# zik-pcb-power.net
KiCad netlist of a schematic drawn in EAGLE
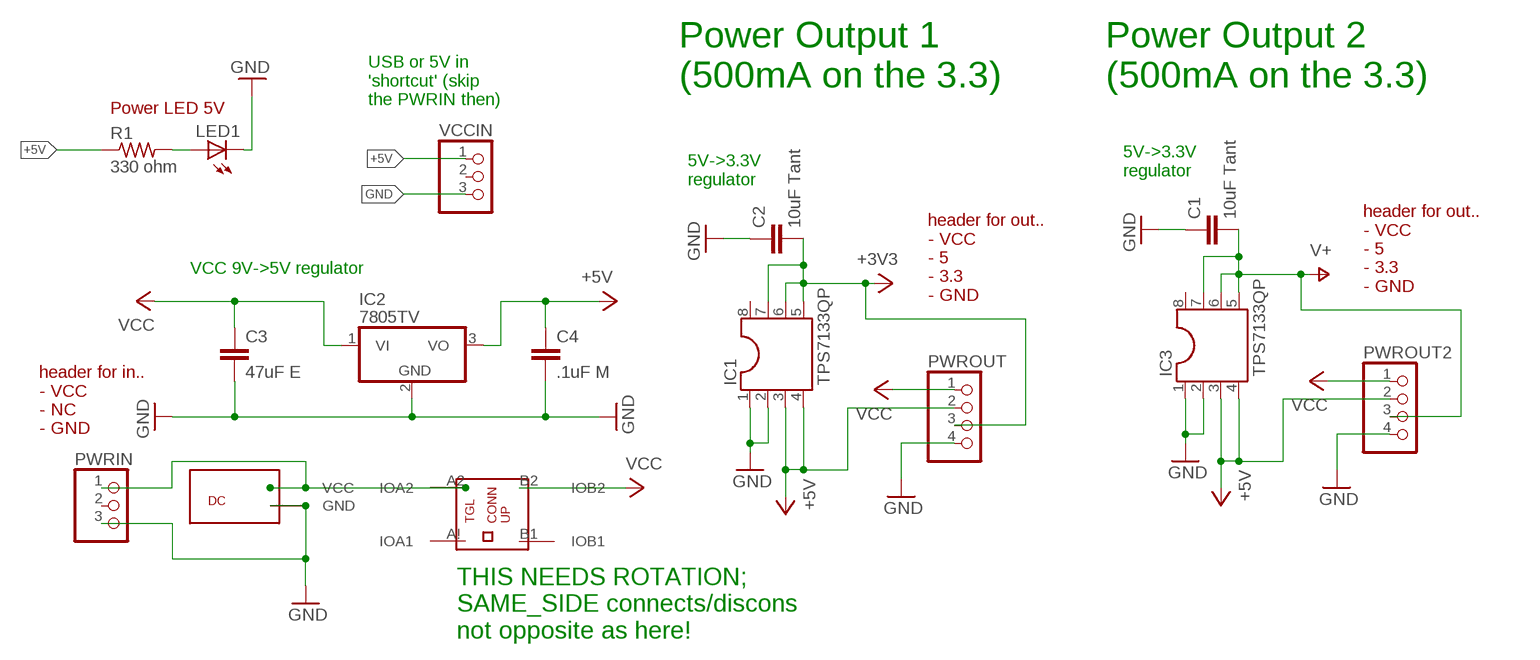
[diagram p0: schematic, sheet 1]

(export (version "E")
  (design (tool "Eeschema 10.0.6"))
  (components
    (comp (ref "C1")
      (value "10uF Tant")
      (footprint "eagle-import:C025-025X050")
      (libsource (lib "eagle-import") (part "C-EU025-025X050"))
    )
    (comp (ref "C2")
      (value "10uF Tant")
      (footprint "eagle-import:C025-025X050")
      (libsource (lib "eagle-import") (part "C-EU025-025X050"))
    )
    (comp (ref "C3")
      (value "47uF E")
      (footprint "eagle-import:C025-025X050")
      (libsource (lib "eagle-import") (part "C-EU025-025X050"))
    )
    (comp (ref "C4")
      (value ".1uF M")
      (footprint "eagle-import:C025-025X050")
      (libsource (lib "eagle-import") (part "C-EU025-025X050"))
    )
    (comp (ref "IC1")
      (value "TPS7133QP")
      (footprint "eagle-import:DIL08")
      (libsource (lib "eagle-import") (part "DIL8"))
    )
    (comp (ref "IC2")
      (value "7805TV")
      (footprint "eagle-import:TO220V")
      (libsource (lib "eagle-import") (part "78TV05"))
    )
    (comp (ref "IC3")
      (value "TPS7133QP")
      (footprint "eagle-import:DIL08")
      (libsource (lib "eagle-import") (part "DIL8"))
    )
    (comp (ref "LED1")
      (value "LED5MM")
      (footprint "eagle-import:LED5MM")
      (libsource (lib "eagle-import") (part "LED5MM"))
    )
    (comp (ref "PWRIN")
      (value "PINHD-1X3")
      (footprint "eagle-import:1X03")
      (libsource (lib "eagle-import") (part "PINHD-1X3"))
    )
    (comp (ref "PWROUT")
      (value "PINHD-1X4")
      (footprint "eagle-import:1X04")
      (libsource (lib "eagle-import") (part "PINHD-1X4"))
    )
    (comp (ref "PWROUT2")
      (value "PINHD-1X4")
      (footprint "eagle-import:1X04")
      (libsource (lib "eagle-import") (part "PINHD-1X4"))
    )
    (comp (ref "R1")
      (value "330 ohm")
      (footprint "eagle-import:0207_10")
      (libsource (lib "eagle-import") (part "R-US_0207/10"))
    )
    (comp (ref "U$1")
      (value "DCJACKZIK")
      (footprint "eagle-import:DCJACKZIK")
      (libsource (lib "eagle-import") (part "DCJACKZIK"))
    )
    (comp (ref "U$2")
      (value "TOGGLE-CYAN-L-ZIK")
      (footprint "eagle-import:TOGGLE-CYAN-LG-ZIK")
      (libsource (lib "eagle-import") (part "TOGGLE-CYAN-L-ZIK"))
    )
    (comp (ref "VCCIN")
      (value "PINHD-1X3")
      (footprint "eagle-import:1X03")
      (libsource (lib "eagle-import") (part "PINHD-1X3"))
    )
  )
  (nets
    (net (code "1") (name "+3V3") (class "Default")
      (node (ref "C2") (pin "2") (pinfunction "2_2") (pintype "passive"))
      (node (ref "IC1") (pin "5") (pinfunction "5_5") (pintype "passive"))
      (node (ref "IC1") (pin "6") (pinfunction "6_6") (pintype "passive"))
      (node (ref "IC1") (pin "7") (pinfunction "7_7") (pintype "passive"))
      (node (ref "PWROUT") (pin "3") (pinfunction "3_3") (pintype "passive"))
    )
    (net (code "2") (name "+5V") (class "Default")
      (node (ref "C4") (pin "1") (pinfunction "1_1") (pintype "passive"))
      (node (ref "IC1") (pin "3") (pinfunction "3_3") (pintype "passive"))
      (node (ref "IC1") (pin "4") (pinfunction "4_4") (pintype "passive"))
      (node (ref "IC2") (pin "3") (pinfunction "VO_3") (pintype "passive"))
      (node (ref "IC3") (pin "3") (pinfunction "3_3") (pintype "passive"))
      (node (ref "IC3") (pin "4") (pinfunction "4_4") (pintype "passive"))
      (node (ref "PWROUT") (pin "2") (pinfunction "2_2") (pintype "passive"))
      (node (ref "PWROUT2") (pin "2") (pinfunction "2_2") (pintype "passive"))
      (node (ref "R1") (pin "1") (pinfunction "1_1") (pintype "passive"))
      (node (ref "VCCIN") (pin "1") (pinfunction "1_1") (pintype "passive"))
    )
    (net (code "3") (name "GND") (class "Default")
      (node (ref "C1") (pin "1") (pinfunction "1_1") (pintype "passive"))
      (node (ref "C2") (pin "1") (pinfunction "1_1") (pintype "passive"))
      (node (ref "C3") (pin "2") (pinfunction "2_2") (pintype "passive"))
      (node (ref "C4") (pin "2") (pinfunction "2_2") (pintype "passive"))
      (node (ref "IC1") (pin "1") (pinfunction "1_1") (pintype "passive"))
      (node (ref "IC1") (pin "2") (pinfunction "2_2") (pintype "passive"))
      (node (ref "IC2") (pin "2") (pinfunction "GND_2") (pintype "passive"))
      (node (ref "IC3") (pin "1") (pinfunction "1_1") (pintype "passive"))
      (node (ref "IC3") (pin "2") (pinfunction "2_2") (pintype "passive"))
      (node (ref "LED1") (pin "K") (pinfunction "C_K") (pintype "passive"))
      (node (ref "PWRIN") (pin "3") (pinfunction "3_3") (pintype "passive"))
      (node (ref "PWROUT") (pin "4") (pinfunction "4_4") (pintype "passive"))
      (node (ref "PWROUT2") (pin "4") (pinfunction "4_4") (pintype "passive"))
      (node (ref "U$1") (pin "JACKET") (pinfunction "GND_JACKET") (pintype "power_in"))
      (node (ref "VCCIN") (pin "3") (pinfunction "3_3") (pintype "passive"))
    )
    (net (code "4") (name "Net-(LED1-PadA)") (class "Default")
      (node (ref "LED1") (pin "A") (pinfunction "A_A") (pintype "passive"))
      (node (ref "R1") (pin "2") (pinfunction "2_2") (pintype "passive"))
    )
    (net (code "5") (name "Net-(U$1-VCC)") (class "Default")
      (node (ref "PWRIN") (pin "1") (pinfunction "1_1") (pintype "passive"))
      (node (ref "U$1") (pin "CPIN") (pinfunction "VCC_CPIN") (pintype "power_in"))
      (node (ref "U$2") (pin "A2") (pinfunction "IOA2_A2") (pintype "bidirectional"))
    )
    (net (code "6") (name "V+") (class "Default")
      (node (ref "C1") (pin "2") (pinfunction "2_2") (pintype "passive"))
      (node (ref "IC3") (pin "5") (pinfunction "5_5") (pintype "passive"))
      (node (ref "IC3") (pin "6") (pinfunction "6_6") (pintype "passive"))
      (node (ref "IC3") (pin "7") (pinfunction "7_7") (pintype "passive"))
      (node (ref "PWROUT2") (pin "3") (pinfunction "3_3") (pintype "passive"))
    )
    (net (code "7") (name "VCC") (class "Default")
      (node (ref "C3") (pin "1") (pinfunction "1_1") (pintype "passive"))
      (node (ref "IC2") (pin "1") (pinfunction "VI_1") (pintype "input"))
      (node (ref "PWROUT") (pin "1") (pinfunction "1_1") (pintype "passive"))
      (node (ref "PWROUT2") (pin "1") (pinfunction "1_1") (pintype "passive"))
      (node (ref "U$2") (pin "B2") (pinfunction "IOB2_B2") (pintype "bidirectional"))
    )
    (net (code "8") (name "unconnected-(IC1-Pad8)") (class "Default")
      (node (ref "IC1") (pin "8") (pinfunction "8_8") (pintype "passive"))
    )
    (net (code "9") (name "unconnected-(IC3-Pad8)") (class "Default")
      (node (ref "IC3") (pin "8") (pinfunction "8_8") (pintype "passive"))
    )
    (net (code "10") (name "unconnected-(PWRIN-Pad2)") (class "Default")
      (node (ref "PWRIN") (pin "2") (pinfunction "2_2") (pintype "passive"))
    )
    (net (code "11") (name "unconnected-(U$2-IOA1-PadA!)") (class "Default")
      (node (ref "U$2") (pin "A!") (pinfunction "IOA1_A!") (pintype "bidirectional"))
    )
    (net (code "12") (name "unconnected-(U$2-IOB1-PadB1)") (class "Default")
      (node (ref "U$2") (pin "B1") (pinfunction "IOB1_B1") (pintype "bidirectional"))
    )
    (net (code "13") (name "unconnected-(VCCIN-Pad2)") (class "Default")
      (node (ref "VCCIN") (pin "2") (pinfunction "2_2") (pintype "passive"))
    )
  )
)
